# powerblade_3v2.net
KiCad netlist of a schematic drawn in EAGLE
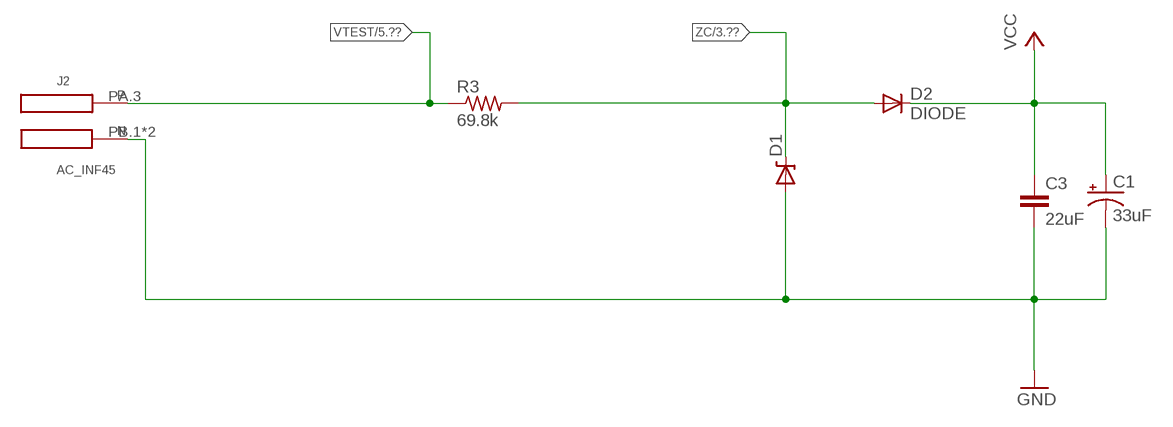
[diagram p0: schematic, sheet 1]
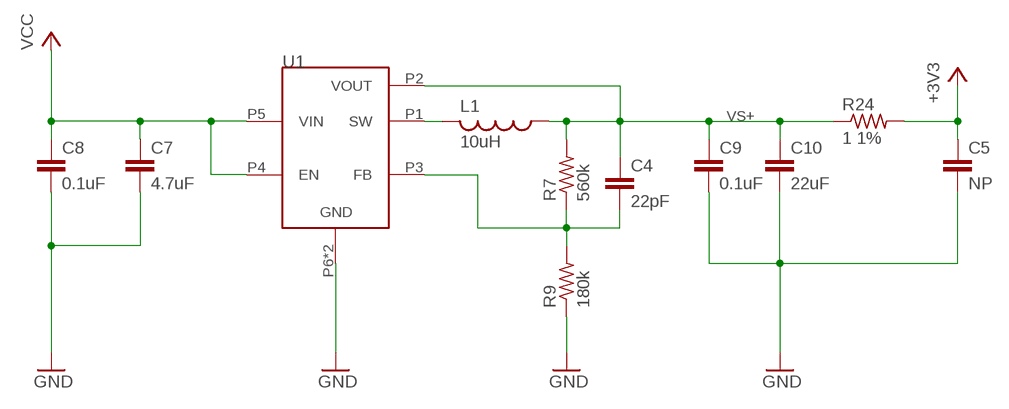
[diagram p1: schematic, sheet 2]
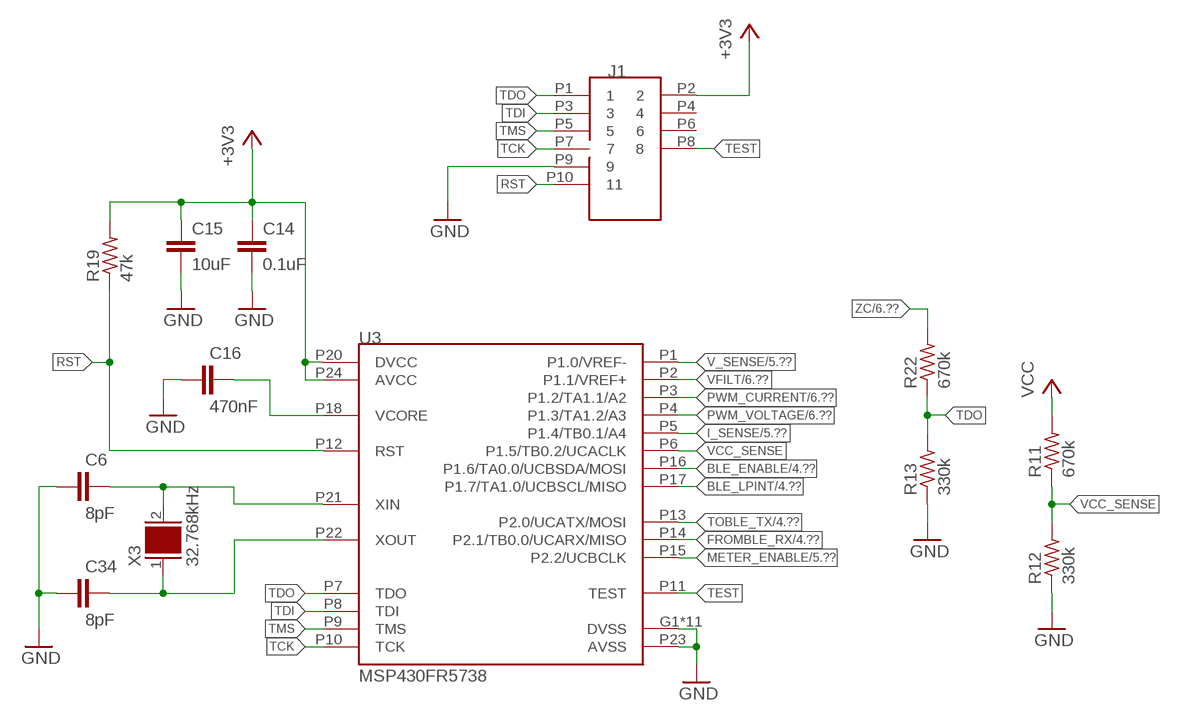
[diagram p2: schematic, sheet 3]
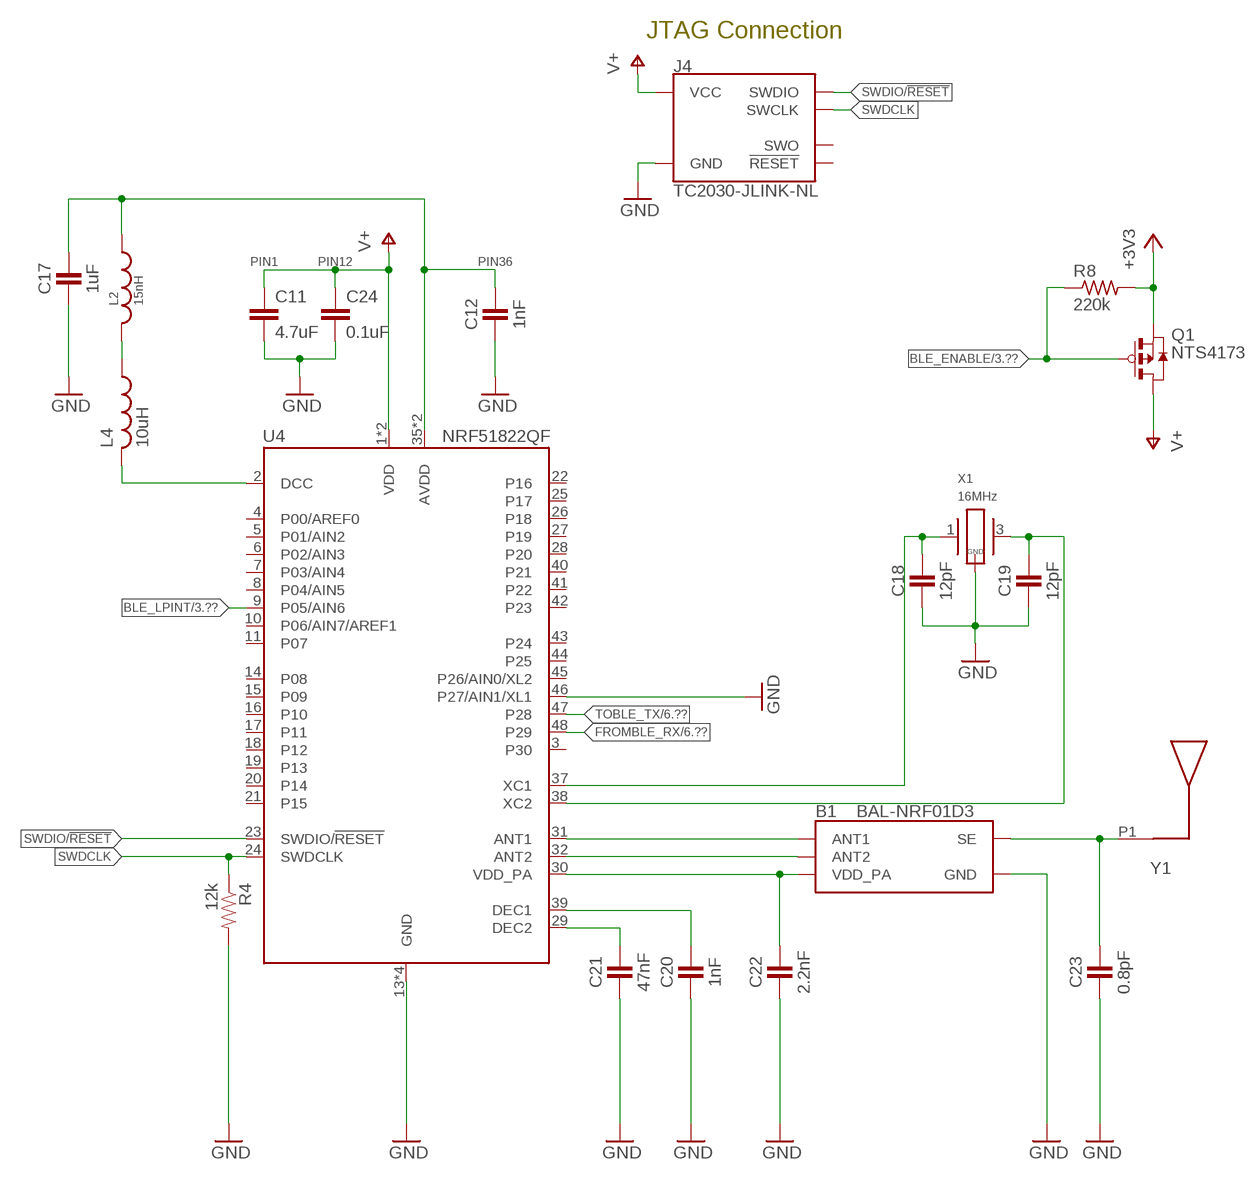
[diagram p3: schematic, sheet 4]
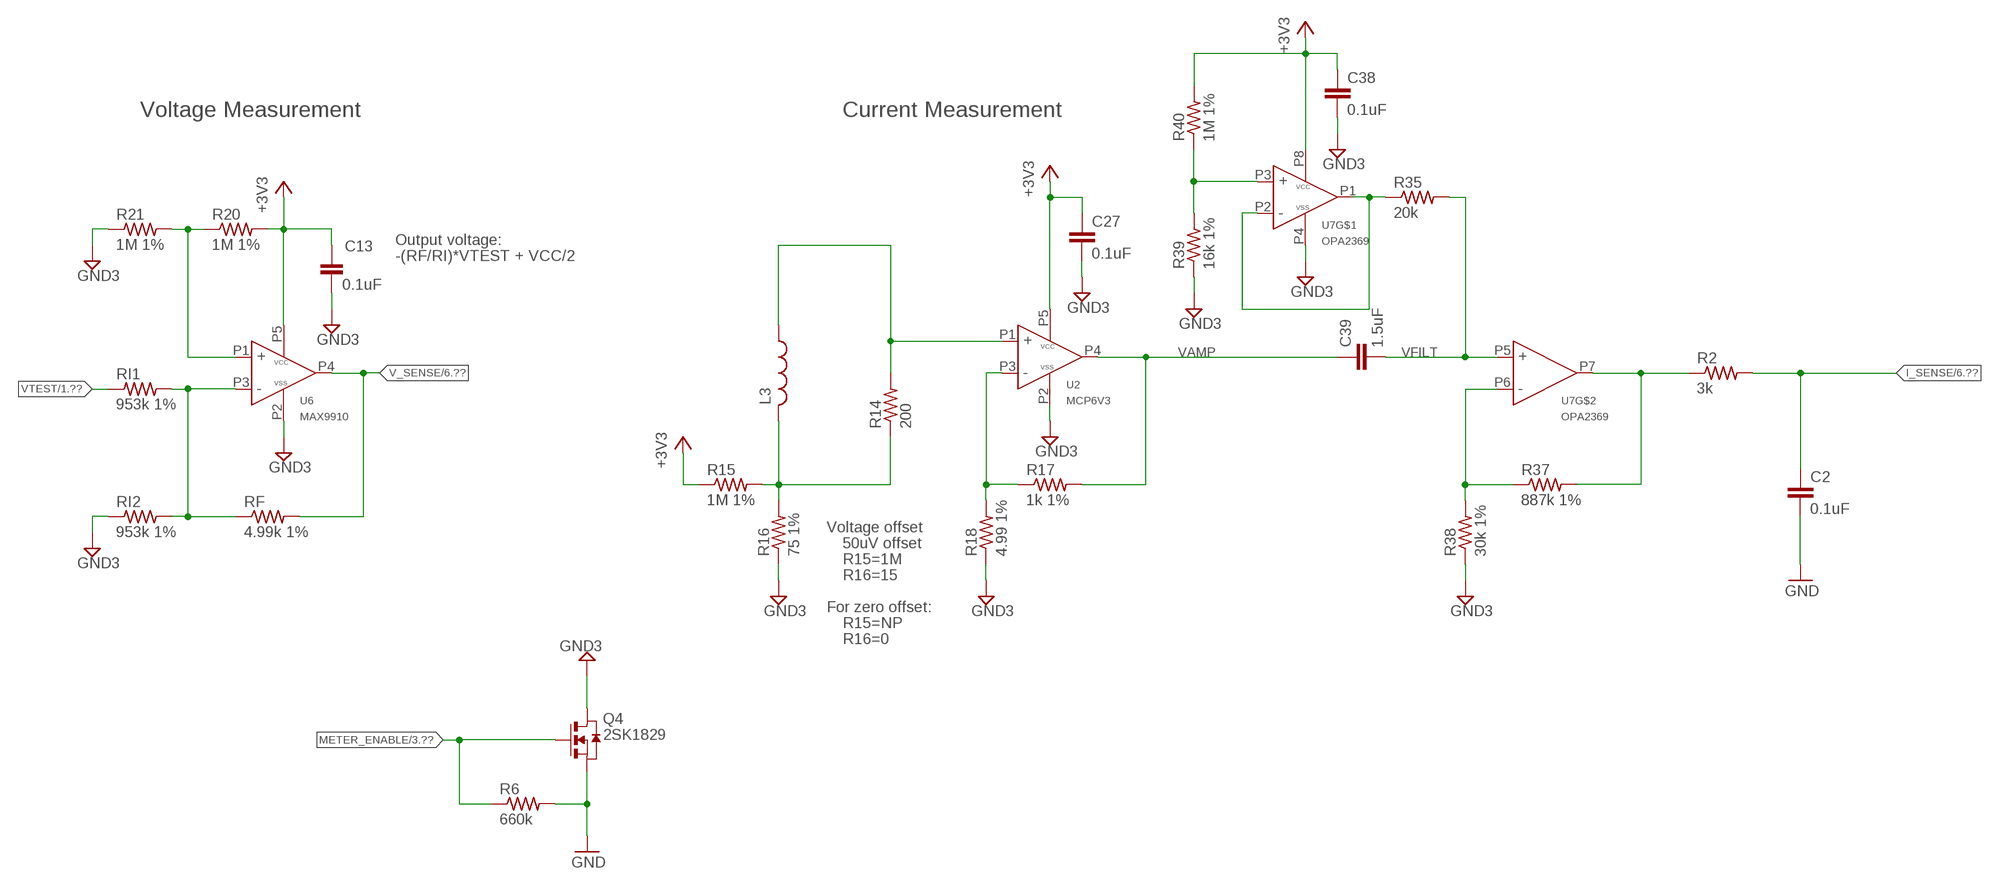
[diagram p4: schematic, sheet 5]
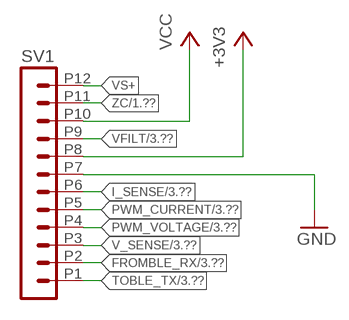
[diagram p5: schematic, sheet 6]

(export (version "E")
  (design (tool "Eeschema 10.0.6"))
  (components
    (comp (ref "C6")
      (value "8pF")
      (footprint "eagle-import:C0402")
      (libsource (lib "eagle-import") (part "C-EUC0402"))
    )
    (comp (ref "C14")
      (value "0.1uF")
      (footprint "eagle-import:C0402")
      (libsource (lib "eagle-import") (part "C-EUC0402"))
    )
    (comp (ref "C15")
      (value "10uF")
      (footprint "eagle-import:C0603_SM")
      (libsource (lib "eagle-import") (part "C-EUC0603_SM"))
    )
    (comp (ref "C16")
      (value "470nF")
      (footprint "eagle-import:C0402")
      (libsource (lib "eagle-import") (part "C-EUC0402"))
    )
    (comp (ref "C34")
      (value "8pF")
      (footprint "eagle-import:C0402")
      (libsource (lib "eagle-import") (part "C-EUC0402"))
    )
    (comp (ref "J1")
      (value "JTAG_14PIN_IDC-ND")
      (footprint "eagle-import:TC2050-IDC-NL-430-ND")
      (libsource (lib "eagle-import") (part "JTAG_14PIN_IDC-ND"))
    )
    (comp (ref "R11")
      (value "670k")
      (footprint "eagle-import:R0402")
      (libsource (lib "eagle-import") (part "R-US_R0402"))
    )
    (comp (ref "R12")
      (value "330k")
      (footprint "eagle-import:R0402")
      (libsource (lib "eagle-import") (part "R-US_R0402"))
    )
    (comp (ref "R13")
      (value "330k")
      (footprint "eagle-import:R0402")
      (libsource (lib "eagle-import") (part "R-US_R0402"))
    )
    (comp (ref "R19")
      (value "47k")
      (footprint "eagle-import:R0402")
      (libsource (lib "eagle-import") (part "R-US_R0402"))
    )
    (comp (ref "R22")
      (value "670k")
      (footprint "eagle-import:R0402")
      (libsource (lib "eagle-import") (part "R-US_R0402"))
    )
    (comp (ref "U3")
      (value "MSP430FR5738")
      (footprint "eagle-import:VQFN-24")
      (libsource (lib "eagle-import") (part "MSP430FR5738"))
    )
    (comp (ref "X3")
      (value "32.768kHz")
      (footprint "eagle-import:0805")
      (libsource (lib "eagle-import") (part "CRYSTAL_0805"))
    )
    (comp (ref "C1")
      (value "33uF")
      (footprint "eagle-import:CPOL0805_SM")
      (libsource (lib "eagle-import") (part "CPOL-US0805_SM"))
    )
    (comp (ref "C3")
      (value "22uF")
      (footprint "eagle-import:C0603_SM")
      (libsource (lib "eagle-import") (part "C-EUC0603_SM"))
    )
    (comp (ref "D1")
      (value "ZENERBZT52")
      (footprint "eagle-import:BZT52")
      (fields (field (name "DIGIKEY") "BZT52C10T-7DICT-ND "))
      (libsource (lib "eagle-import") (part "ZENERBZT52"))
    )
    (comp (ref "D2")
      (value "DIODE")
      (footprint "eagle-import:BAS521")
      (libsource (lib "eagle-import") (part "DIODE"))
    )
    (comp (ref "J2")
      (value "AC_INF45")
      (footprint "eagle-import:AC3_F45")
      (libsource (lib "eagle-import") (part "AC_INF45"))
    )
    (comp (ref "R3")
      (value "69.8k")
      (footprint "eagle-import:R1210")
      (libsource (lib "eagle-import") (part "R-US_R1210"))
    )
    (comp (ref "C4")
      (value "22pF")
      (footprint "eagle-import:C0402")
      (libsource (lib "eagle-import") (part "C-EUC0402"))
    )
    (comp (ref "C5")
      (value "NP")
      (footprint "eagle-import:C0603_TN")
      (libsource (lib "eagle-import") (part "C-EUC0603_TN"))
    )
    (comp (ref "C7")
      (value "4.7uF")
      (footprint "eagle-import:C0402")
      (libsource (lib "eagle-import") (part "C-EUC0402"))
    )
    (comp (ref "C8")
      (value "0.1uF")
      (footprint "eagle-import:C0402")
      (libsource (lib "eagle-import") (part "C-EUC0402"))
    )
    (comp (ref "C9")
      (value "0.1uF")
      (footprint "eagle-import:C0402_SM")
      (libsource (lib "eagle-import") (part "C-EUC0402_SM"))
    )
    (comp (ref "C10")
      (value "22uF")
      (footprint "eagle-import:C0603_SM")
      (libsource (lib "eagle-import") (part "C-EUC0603_SM"))
    )
    (comp (ref "L1")
      (value "10uH")
      (footprint "eagle-import:L0805")
      (libsource (lib "eagle-import") (part "L-USL0805"))
    )
    (comp (ref "R7")
      (value "560k")
      (footprint "eagle-import:R0402")
      (libsource (lib "eagle-import") (part "R-US_R0402"))
    )
    (comp (ref "R9")
      (value "180k")
      (footprint "eagle-import:R0402")
      (libsource (lib "eagle-import") (part "R-US_R0402"))
    )
    (comp (ref "R24")
      (value "1 1%")
      (footprint "eagle-import:R0603_SM")
      (libsource (lib "eagle-import") (part "R-US_R0603_SM"))
    )
    (comp (ref "U1")
      (value "TPS62122")
      (footprint "eagle-import:WDFN-6")
      (libsource (lib "eagle-import") (part "TPS62122"))
    )
    (comp (ref "SV1")
      (value "MA12-11M27")
      (footprint "eagle-import:MA12-1_1MM27")
      (libsource (lib "eagle-import") (part "MA12-11M27"))
    )
    (comp (ref "B1")
      (value "BAL-NRF01D3")
      (footprint "eagle-import:BAL-NRF01D3")
      (libsource (lib "eagle-import") (part "BAL-NRF01D3"))
    )
    (comp (ref "C11")
      (value "4.7uF")
      (footprint "eagle-import:C0402")
      (libsource (lib "eagle-import") (part "C-EUC0402"))
    )
    (comp (ref "C12")
      (value "1nF")
      (footprint "eagle-import:0402_CAP")
      (libsource (lib "eagle-import") (part "CAPACITOR"))
    )
    (comp (ref "C17")
      (value "1uF")
      (footprint "eagle-import:0402_CAP")
      (libsource (lib "eagle-import") (part "CAPACITOR"))
    )
    (comp (ref "C18")
      (value "12pF")
      (footprint "eagle-import:0402_CAP")
      (libsource (lib "eagle-import") (part "CAPACITOR"))
    )
    (comp (ref "C19")
      (value "12pF")
      (footprint "eagle-import:0402_CAP")
      (libsource (lib "eagle-import") (part "CAPACITOR"))
    )
    (comp (ref "C20")
      (value "1nF")
      (footprint "eagle-import:0402_CAP")
      (libsource (lib "eagle-import") (part "CAPACITOR"))
    )
    (comp (ref "C21")
      (value "47nF")
      (footprint "eagle-import:0402_CAP")
      (libsource (lib "eagle-import") (part "CAPACITOR"))
    )
    (comp (ref "C22")
      (value "2.2nF")
      (footprint "eagle-import:0402_CAP")
      (libsource (lib "eagle-import") (part "CAPACITOR"))
    )
    (comp (ref "C23")
      (value "0.8pF")
      (footprint "eagle-import:0402_CAP")
      (libsource (lib "eagle-import") (part "CAPACITOR"))
    )
    (comp (ref "C24")
      (value "0.1uF")
      (footprint "eagle-import:C0402")
      (libsource (lib "eagle-import") (part "C-EUC0402"))
    )
    (comp (ref "J4")
      (value "TC2030-JLINK-NL")
      (footprint "eagle-import:TC2030-IDC-NL")
      (libsource (lib "eagle-import") (part "TC2030-JLINK-NL"))
    )
    (comp (ref "L2")
      (value "15nH")
      (footprint "eagle-import:0402_CAP")
      (libsource (lib "eagle-import") (part "INDUCTOR0402"))
    )
    (comp (ref "L4")
      (value "10uH")
      (footprint "eagle-import:C0603_TN")
      (libsource (lib "eagle-import") (part "L-USL0603_TN"))
    )
    (comp (ref "Q1")
      (value "NTS4173")
      (footprint "eagle-import:SC-70-3")
      (libsource (lib "eagle-import") (part "NTS4173"))
    )
    (comp (ref "R4")
      (value "12k")
      (footprint "eagle-import:0402_RES")
      (libsource (lib "eagle-import") (part "RESISTOR"))
    )
    (comp (ref "R8")
      (value "220k")
      (footprint "eagle-import:R0402_SM")
      (libsource (lib "eagle-import") (part "R-US_R0402_SM"))
    )
    (comp (ref "U4")
      (value "NRF51822QF")
      (footprint "eagle-import:QFN-48-6MM")
      (libsource (lib "eagle-import") (part "NRF51822QF"))
    )
    (comp (ref "X1")
      (value "16MHz")
      (footprint "eagle-import:TXC-8Y")
      (libsource (lib "eagle-import") (part "TXC-8Y"))
    )
    (comp (ref "Y1")
      (value "UREACH_XTEND")
      (footprint "eagle-import:UREACH_XTEND")
      (libsource (lib "eagle-import") (part "UREACH_XTEND"))
    )
    (comp (ref "C2")
      (value "0.1uF")
      (footprint "eagle-import:C0402")
      (libsource (lib "eagle-import") (part "C-EUC0402"))
    )
    (comp (ref "C13")
      (value "0.1uF")
      (footprint "eagle-import:0402_CAP")
      (libsource (lib "eagle-import") (part "CAPACITOR"))
    )
    (comp (ref "C27")
      (value "0.1uF")
      (footprint "eagle-import:C0402")
      (libsource (lib "eagle-import") (part "C-EUC0402"))
    )
    (comp (ref "C38")
      (value "0.1uF")
      (footprint "eagle-import:C0402")
      (libsource (lib "eagle-import") (part "C-EUC0402"))
    )
    (comp (ref "C39")
      (value "1.5uF")
      (footprint "eagle-import:C0402")
      (libsource (lib "eagle-import") (part "C-EUC0402"))
    )
    (comp (ref "L3")
      (value "L-USL0805")
      (footprint "eagle-import:L0805")
      (libsource (lib "eagle-import") (part "L-USL0805"))
    )
    (comp (ref "Q4")
      (value "2SK1829")
      (footprint "eagle-import:SC-70-3")
      (libsource (lib "eagle-import") (part "2SK1829"))
    )
    (comp (ref "R2")
      (value "3k")
      (footprint "eagle-import:R0402_SM")
      (libsource (lib "eagle-import") (part "R-US_R0402_SM"))
    )
    (comp (ref "R6")
      (value "660k")
      (footprint "eagle-import:R0402")
      (libsource (lib "eagle-import") (part "R-US_R0402"))
    )
    (comp (ref "R14")
      (value "200")
      (footprint "eagle-import:R0402")
      (libsource (lib "eagle-import") (part "R-US_R0402"))
    )
    (comp (ref "R15")
      (value "1M 1%")
      (footprint "eagle-import:R0402")
      (libsource (lib "eagle-import") (part "R-US_R0402"))
    )
    (comp (ref "R16")
      (value "75 1%")
      (footprint "eagle-import:R0402")
      (libsource (lib "eagle-import") (part "R-US_R0402"))
    )
    (comp (ref "R17")
      (value "1k 1%")
      (footprint "eagle-import:R0402")
      (libsource (lib "eagle-import") (part "R-US_R0402"))
    )
    (comp (ref "R18")
      (value "4.99 1%")
      (footprint "eagle-import:R0402")
      (libsource (lib "eagle-import") (part "R-US_R0402"))
    )
    (comp (ref "R20")
      (value "1M 1%")
      (footprint "eagle-import:R0402")
      (libsource (lib "eagle-import") (part "R-US_R0402"))
    )
    (comp (ref "R21")
      (value "1M 1%")
      (footprint "eagle-import:R0402_SM")
      (libsource (lib "eagle-import") (part "R-US_R0402_SM"))
    )
    (comp (ref "R35")
      (value "20k")
      (footprint "eagle-import:R0402")
      (libsource (lib "eagle-import") (part "R-US_R0402"))
    )
    (comp (ref "R37")
      (value "887k 1%")
      (footprint "eagle-import:R0402")
      (libsource (lib "eagle-import") (part "R-US_R0402"))
    )
    (comp (ref "R38")
      (value "30k 1%")
      (footprint "eagle-import:R0402")
      (libsource (lib "eagle-import") (part "R-US_R0402"))
    )
    (comp (ref "R39")
      (value "16k 1%")
      (footprint "eagle-import:R0402")
      (libsource (lib "eagle-import") (part "R-US_R0402"))
    )
    (comp (ref "R40")
      (value "1M 1%")
      (footprint "eagle-import:R0402")
      (libsource (lib "eagle-import") (part "R-US_R0402"))
    )
    (comp (ref "RF")
      (value "4.99k 1%")
      (footprint "eagle-import:R0402")
      (libsource (lib "eagle-import") (part "R-US_R0402"))
    )
    (comp (ref "RI1")
      (value "953k 1%")
      (footprint "eagle-import:R0402")
      (libsource (lib "eagle-import") (part "R-US_R0402"))
    )
    (comp (ref "RI2")
      (value "953k 1%")
      (footprint "eagle-import:R0402")
      (libsource (lib "eagle-import") (part "R-US_R0402"))
    )
    (comp (ref "U2")
      (value "MCP6V3")
      (footprint "eagle-import:SC70-5")
      (fields (field (name "DIGIKEY") "296-19547-1-ND"))
      (libsource (lib "eagle-import") (part "MCP6V3"))
    )
    (comp (ref "U6")
      (value "MAX9910")
      (footprint "eagle-import:SC70-5")
      (fields (field (name "DIGIKEY") "296-25252-1-ND"))
      (libsource (lib "eagle-import") (part "MAX9910"))
    )
    (comp (ref "U7")
      (value "OPA2369")
      (footprint "eagle-import:SOT-23-8")
      (libsource (lib "eagle-import") (part "OPA2369"))
    )
  )
  (nets
    (net (code "1") (name "+3V3") (class "Default")
      (node (ref "C13") (pin "1") (pinfunction "1_1") (pintype "bidirectional"))
      (node (ref "C14") (pin "1") (pinfunction "1_1") (pintype "passive"))
      (node (ref "C15") (pin "1") (pinfunction "1_1") (pintype "passive"))
      (node (ref "C27") (pin "1") (pinfunction "1_1") (pintype "passive"))
      (node (ref "C38") (pin "1") (pinfunction "1_1") (pintype "passive"))
      (node (ref "C5") (pin "1") (pinfunction "1_1") (pintype "passive"))
      (node (ref "J1") (pin "P2") (pinfunction "2_P2") (pintype "bidirectional"))
      (node (ref "Q1") (pin "P2") (pinfunction "S_P2") (pintype "passive"))
      (node (ref "R15") (pin "1") (pinfunction "1_1") (pintype "passive"))
      (node (ref "R19") (pin "2") (pinfunction "2_2") (pintype "passive"))
      (node (ref "R20") (pin "2") (pinfunction "2_2") (pintype "passive"))
      (node (ref "R24") (pin "2") (pinfunction "2_2") (pintype "passive"))
      (node (ref "R40") (pin "2") (pinfunction "2_2") (pintype "passive"))
      (node (ref "R8") (pin "2") (pinfunction "2_2") (pintype "passive"))
      (node (ref "SV1") (pin "P8") (pinfunction "8_P8") (pintype "passive"))
      (node (ref "U2") (pin "P5") (pinfunction "VCC_P5") (pintype "bidirectional"))
      (node (ref "U3") (pin "P20") (pinfunction "DVCC_P20") (pintype "bidirectional"))
      (node (ref "U3") (pin "P24") (pinfunction "AVCC_P24") (pintype "bidirectional"))
      (node (ref "U6") (pin "P5") (pinfunction "VCC_P5") (pintype "bidirectional"))
      (node (ref "U7") (pin "P8") (pinfunction "VCC_P8") (pintype "bidirectional"))
    )
    (net (code "2") (name "BLE_ENABLE") (class "Default")
      (node (ref "Q1") (pin "P1") (pinfunction "G_P1") (pintype "passive"))
      (node (ref "R8") (pin "1") (pinfunction "1_1") (pintype "passive"))
      (node (ref "U3") (pin "P16") (pinfunction "P1.6/TA0.0/UCBSDA/MOSI_P16") (pintype "bidirectional"))
    )
    (net (code "3") (name "BLE_LPINT") (class "Default")
      (node (ref "U3") (pin "P17") (pinfunction "P1.7/TA1.0/UCBSCL/MISO_P17") (pintype "bidirectional"))
      (node (ref "U4") (pin "9") (pinfunction "P05/AIN6_9") (pintype "bidirectional"))
    )
    (net (code "4") (name "FROMBLE_RX") (class "Default")
      (node (ref "SV1") (pin "P2") (pinfunction "2_P2") (pintype "passive"))
      (node (ref "U3") (pin "P14") (pinfunction "P2.1/TB0.0/UCARX/MISO_P14") (pintype "bidirectional"))
      (node (ref "U4") (pin "48") (pinfunction "P29_48") (pintype "bidirectional"))
    )
    (net (code "5") (name "GND") (class "Default")
      (node (ref "B1") (pin "GND") (pinfunction "GND_GND") (pintype "bidirectional"))
      (node (ref "C1") (pin "-") (pinfunction "-_-") (pintype "passive"))
      (node (ref "C10") (pin "2") (pinfunction "2_2") (pintype "passive"))
      (node (ref "C11") (pin "2") (pinfunction "2_2") (pintype "passive"))
      (node (ref "C12") (pin "2") (pinfunction "2_2") (pintype "bidirectional"))
      (node (ref "C14") (pin "2") (pinfunction "2_2") (pintype "passive"))
      (node (ref "C15") (pin "2") (pinfunction "2_2") (pintype "passive"))
      (node (ref "C16") (pin "1") (pinfunction "1_1") (pintype "passive"))
      (node (ref "C17") (pin "2") (pinfunction "2_2") (pintype "bidirectional"))
      (node (ref "C18") (pin "2") (pinfunction "2_2") (pintype "bidirectional"))
      (node (ref "C19") (pin "2") (pinfunction "2_2") (pintype "bidirectional"))
      (node (ref "C2") (pin "2") (pinfunction "2_2") (pintype "passive"))
      (node (ref "C20") (pin "2") (pinfunction "2_2") (pintype "bidirectional"))
      (node (ref "C21") (pin "2") (pinfunction "2_2") (pintype "bidirectional"))
      (node (ref "C22") (pin "2") (pinfunction "2_2") (pintype "bidirectional"))
      (node (ref "C23") (pin "2") (pinfunction "2_2") (pintype "bidirectional"))
      (node (ref "C24") (pin "2") (pinfunction "2_2") (pintype "passive"))
      (node (ref "C3") (pin "2") (pinfunction "2_2") (pintype "passive"))
      (node (ref "C34") (pin "1") (pinfunction "1_1") (pintype "passive"))
      (node (ref "C5") (pin "2") (pinfunction "2_2") (pintype "passive"))
      (node (ref "C6") (pin "1") (pinfunction "1_1") (pintype "passive"))
      (node (ref "C7") (pin "2") (pinfunction "2_2") (pintype "passive"))
      (node (ref "C8") (pin "2") (pinfunction "2_2") (pintype "passive"))
      (node (ref "C9") (pin "2") (pinfunction "2_2") (pintype "passive"))
      (node (ref "D1") (pin "A") (pinfunction "A_A") (pintype "passive"))
      (node (ref "J1") (pin "P9") (pinfunction "9_P9") (pintype "bidirectional"))
      (node (ref "J2") (pin "PB.1") (pinfunction "N_PB.1") (pintype "bidirectional"))
      (node (ref "J2") (pin "PB.3") (pinfunction "N_PB.3") (pintype "bidirectional"))
      (node (ref "J4") (pin "5") (pinfunction "GND_5") (pintype "bidirectional"))
      (node (ref "Q4") (pin "P2") (pinfunction "S_P2") (pintype "passive"))
      (node (ref "R12") (pin "1") (pinfunction "1_1") (pintype "passive"))
      (node (ref "R13") (pin "1") (pinfunction "1_1") (pintype "passive"))
      (node (ref "R4") (pin "2") (pinfunction "2_2") (pintype "passive"))
      (node (ref "R6") (pin "2") (pinfunction "2_2") (pintype "passive"))
      (node (ref "R9") (pin "1") (pinfunction "1_1") (pintype "passive"))
      (node (ref "SV1") (pin "P7") (pinfunction "7_P7") (pintype "passive"))
      (node (ref "U1") (pin "P6") (pinfunction "GND_P6") (pintype "bidirectional"))
      (node (ref "U1") (pin "PAD") (pinfunction "GND_PAD") (pintype "bidirectional"))
      (node (ref "U3") (pin "G1") (pinfunction "DVSS_G1") (pintype "bidirectional"))
      (node (ref "U3") (pin "G2") (pinfunction "DVSS_G2") (pintype "bidirectional"))
      (node (ref "U3") (pin "G3") (pinfunction "DVSS_G3") (pintype "bidirectional"))
      (node (ref "U3") (pin "G4") (pinfunction "DVSS_G4") (pintype "bidirectional"))
      (node (ref "U3") (pin "G5") (pinfunction "DVSS_G5") (pintype "bidirectional"))
      (node (ref "U3") (pin "G6") (pinfunction "DVSS_G6") (pintype "bidirectional"))
      (node (ref "U3") (pin "G7") (pinfunction "DVSS_G7") (pintype "bidirectional"))
      (node (ref "U3") (pin "G8") (pinfunction "DVSS_G8") (pintype "bidirectional"))
      (node (ref "U3") (pin "G9") (pinfunction "DVSS_G9") (pintype "bidirectional"))
      (node (ref "U3") (pin "P19") (pinfunction "DVSS_P19") (pintype "bidirectional"))
      (node (ref "U3") (pin "P23") (pinfunction "AVSS_P23") (pintype "bidirectional"))
      (node (ref "U3") (pin "PAD") (pinfunction "DVSS_PAD") (pintype "bidirectional"))
      (node (ref "U4") (pin "13") (pinfunction "GND_13") (pintype "bidirectional"))
      (node (ref "U4") (pin "33") (pinfunction "GND_33") (pintype "bidirectional"))
      (node (ref "U4") (pin "34") (pinfunction "GND_34") (pintype "bidirectional"))
      (node (ref "U4") (pin "46") (pinfunction "P27/AIN1/XL1_46") (pintype "bidirectional"))
      (node (ref "U4") (pin "GND") (pinfunction "GND_GND") (pintype "bidirectional"))
      (node (ref "X1") (pin "2") (pinfunction "GND_2") (pintype "bidirectional"))
      (node (ref "X1") (pin "4") (pinfunction "GND_4") (pintype "bidirectional"))
    )
    (net (code "6") (name "GND3") (class "Default")
      (node (ref "C13") (pin "2") (pinfunction "2_2") (pintype "bidirectional"))
      (node (ref "C27") (pin "2") (pinfunction "2_2") (pintype "passive"))
      (node (ref "C38") (pin "2") (pinfunction "2_2") (pintype "passive"))
      (node (ref "Q4") (pin "P3") (pinfunction "D_P3") (pintype "passive"))
      (node (ref "R16") (pin "1") (pinfunction "1_1") (pintype "passive"))
      (node (ref "R18") (pin "1") (pinfunction "1_1") (pintype "passive"))
      (node (ref "R21") (pin "1") (pinfunction "1_1") (pintype "passive"))
      (node (ref "R38") (pin "1") (pinfunction "1_1") (pintype "passive"))
      (node (ref "R39") (pin "1") (pinfunction "1_1") (pintype "passive"))
      (node (ref "RI2") (pin "1") (pinfunction "1_1") (pintype "passive"))
      (node (ref "U2") (pin "P2") (pinfunction "VSS_P2") (pintype "bidirectional"))
      (node (ref "U6") (pin "P2") (pinfunction "VSS_P2") (pintype "bidirectional"))
      (node (ref "U7") (pin "P4") (pinfunction "VSS_P4") (pintype "bidirectional"))
    )
    (net (code "7") (name "I_SENSE") (class "Default")
      (node (ref "C2") (pin "1") (pinfunction "1_1") (pintype "passive"))
      (node (ref "R2") (pin "2") (pinfunction "2_2") (pintype "passive"))
      (node (ref "SV1") (pin "P6") (pinfunction "6_P6") (pintype "passive"))
      (node (ref "U3") (pin "P5") (pinfunction "P1.4/TB0.1/A4_P5") (pintype "bidirectional"))
    )
    (net (code "8") (name "METER_ENABLE") (class "Default")
      (node (ref "Q4") (pin "P1") (pinfunction "G_P1") (pintype "passive"))
      (node (ref "R6") (pin "1") (pinfunction "1_1") (pintype "passive"))
      (node (ref "U3") (pin "P15") (pinfunction "P2.2/UCBCLK_P15") (pintype "bidirectional"))
    )
    (net (code "9") (name "Net-(B1-PadSE)") (class "Default")
      (node (ref "B1") (pin "SE") (pinfunction "SE_SE") (pintype "bidirectional"))
      (node (ref "C23") (pin "1") (pinfunction "1_1") (pintype "bidirectional"))
      (node (ref "Y1") (pin "P1") (pinfunction "P1_P1") (pintype "bidirectional"))
    )
    (net (code "10") (name "Net-(B1-VDD_PA)") (class "Default")
      (node (ref "B1") (pin "VCC") (pinfunction "VDD_PA_VCC") (pintype "bidirectional"))
      (node (ref "C22") (pin "1") (pinfunction "1_1") (pintype "bidirectional"))
      (node (ref "U4") (pin "30") (pinfunction "VDD_PA_30") (pintype "bidirectional"))
    )
    (net (code "11") (name "Net-(C12-Pad1)") (class "Default")
      (node (ref "C12") (pin "1") (pinfunction "1_1") (pintype "bidirectional"))
      (node (ref "C17") (pin "1") (pinfunction "1_1") (pintype "bidirectional"))
      (node (ref "L2") (pin "1") (pinfunction "1_1") (pintype "bidirectional"))
      (node (ref "U4") (pin "35") (pinfunction "AVDD_35") (pintype "bidirectional"))
      (node (ref "U4") (pin "36") (pinfunction "AVDD_36") (pintype "bidirectional"))
    )
    (net (code "12") (name "Net-(L2-Pad2)") (class "Default")
      (node (ref "L2") (pin "2") (pinfunction "2_2") (pintype "bidirectional"))
      (node (ref "L4") (pin "1") (pinfunction "1_1") (pintype "passive"))
    )
    (net (code "13") (name "Net-(L3-Pad2)") (class "Default")
      (node (ref "L3") (pin "2") (pinfunction "2_2") (pintype "passive"))
      (node (ref "R14") (pin "1") (pinfunction "1_1") (pintype "passive"))
      (node (ref "R15") (pin "2") (pinfunction "2_2") (pintype "passive"))
      (node (ref "R16") (pin "2") (pinfunction "2_2") (pintype "passive"))
    )
    (net (code "14") (name "Net-(U1-FB)") (class "Default")
      (node (ref "C4") (pin "2") (pinfunction "2_2") (pintype "passive"))
      (node (ref "R7") (pin "1") (pinfunction "1_1") (pintype "passive"))
      (node (ref "R9") (pin "2") (pinfunction "2_2") (pintype "passive"))
      (node (ref "U1") (pin "P3") (pinfunction "FB_P3") (pintype "bidirectional"))
    )
    (net (code "15") (name "Net-(U1-SW)") (class "Default")
      (node (ref "L1") (pin "2") (pinfunction "2_2") (pintype "passive"))
      (node (ref "U1") (pin "P1") (pinfunction "SW_P1") (pintype "bidirectional"))
    )
    (net (code "16") (name "Net-(U2-IN+)") (class "Default")
      (node (ref "L3") (pin "1") (pinfunction "1_1") (pintype "passive"))
      (node (ref "R14") (pin "2") (pinfunction "2_2") (pintype "passive"))
      (node (ref "U2") (pin "P1") (pinfunction "IN+_P1") (pintype "bidirectional"))
    )
    (net (code "17") (name "Net-(U2-IN-)") (class "Default")
      (node (ref "R17") (pin "1") (pinfunction "1_1") (pintype "passive"))
      (node (ref "R18") (pin "2") (pinfunction "2_2") (pintype "passive"))
      (node (ref "U2") (pin "P3") (pinfunction "IN-_P3") (pintype "bidirectional"))
    )
    (net (code "18") (name "Net-(U3-VCORE)") (class "Default")
      (node (ref "C16") (pin "2") (pinfunction "2_2") (pintype "passive"))
      (node (ref "U3") (pin "P18") (pinfunction "VCORE_P18") (pintype "bidirectional"))
    )
    (net (code "19") (name "Net-(U3-XIN)") (class "Default")
      (node (ref "C6") (pin "2") (pinfunction "2_2") (pintype "passive"))
      (node (ref "U3") (pin "P21") (pinfunction "XIN_P21") (pintype "bidirectional"))
      (node (ref "X3") (pin "2") (pinfunction "P2_2") (pintype "bidirectional"))
    )
    (net (code "20") (name "Net-(U3-XOUT)") (class "Default")
      (node (ref "C34") (pin "2") (pinfunction "2_2") (pintype "passive"))
      (node (ref "U3") (pin "P22") (pinfunction "XOUT_P22") (pintype "bidirectional"))
      (node (ref "X3") (pin "1") (pinfunction "P1_1") (pintype "bidirectional"))
    )
    (net (code "21") (name "Net-(U4-ANT1)") (class "Default")
      (node (ref "B1") (pin "ANT1") (pinfunction "ANT1_ANT1") (pintype "bidirectional"))
      (node (ref "U4") (pin "31") (pinfunction "ANT1_31") (pintype "bidirectional"))
    )
    (net (code "22") (name "Net-(U4-ANT2)") (class "Default")
      (node (ref "B1") (pin "ANT2") (pinfunction "ANT2_ANT2") (pintype "bidirectional"))
      (node (ref "U4") (pin "32") (pinfunction "ANT2_32") (pintype "bidirectional"))
    )
    (net (code "23") (name "Net-(U4-DCC)") (class "Default")
      (node (ref "L4") (pin "2") (pinfunction "2_2") (pintype "passive"))
      (node (ref "U4") (pin "2") (pinfunction "DCC_2") (pintype "bidirectional"))
    )
    (net (code "24") (name "Net-(U4-DEC1)") (class "Default")
      (node (ref "C20") (pin "1") (pinfunction "1_1") (pintype "bidirectional"))
      (node (ref "U4") (pin "39") (pinfunction "DEC1_39") (pintype "bidirectional"))
    )
    (net (code "25") (name "Net-(U4-DEC2)") (class "Default")
      (node (ref "C21") (pin "1") (pinfunction "1_1") (pintype "bidirectional"))
      (node (ref "U4") (pin "29") (pinfunction "DEC2_29") (pintype "bidirectional"))
    )
    (net (code "26") (name "Net-(U4-XC1)") (class "Default")
      (node (ref "C18") (pin "1") (pinfunction "1_1") (pintype "bidirectional"))
      (node (ref "U4") (pin "37") (pinfunction "XC1_37") (pintype "bidirectional"))
      (node (ref "X1") (pin "1") (pinfunction "1_1") (pintype "bidirectional"))
    )
    (net (code "27") (name "Net-(U4-XC2)") (class "Default")
      (node (ref "C19") (pin "1") (pinfunction "1_1") (pintype "bidirectional"))
      (node (ref "U4") (pin "38") (pinfunction "XC2_38") (pintype "bidirectional"))
      (node (ref "X1") (pin "3") (pinfunction "2_3") (pintype "bidirectional"))
    )
    (net (code "28") (name "Net-(U6-IN+)") (class "Default")
      (node (ref "R20") (pin "1") (pinfunction "1_1") (pintype "passive"))
      (node (ref "R21") (pin "2") (pinfunction "2_2") (pintype "passive"))
      (node (ref "U6") (pin "P1") (pinfunction "IN+_P1") (pintype "bidirectional"))
    )
    (net (code "29") (name "Net-(U6-IN-)") (class "Default")
      (node (ref "RF") (pin "1") (pinfunction "1_1") (pintype "passive"))
      (node (ref "RI1") (pin "2") (pinfunction "2_2") (pintype "passive"))
      (node (ref "RI2") (pin "2") (pinfunction "2_2") (pintype "passive"))
      (node (ref "U6") (pin "P3") (pinfunction "IN-_P3") (pintype "bidirectional"))
    )
    (net (code "30") (name "Net-(U7A-IN+)") (class "Default")
      (node (ref "R39") (pin "2") (pinfunction "2_2") (pintype "passive"))
      (node (ref "R40") (pin "1") (pinfunction "1_1") (pintype "passive"))
      (node (ref "U7") (pin "P3") (pinfunction "IN+_P3") (pintype "bidirectional"))
    )
    (net (code "31") (name "Net-(U7A-IN-)") (class "Default")
      (node (ref "R35") (pin "1") (pinfunction "1_1") (pintype "passive"))
      (node (ref "U7") (pin "P1") (pinfunction "OUT_P1") (pintype "bidirectional"))
      (node (ref "U7") (pin "P2") (pinfunction "IN-_P2") (pintype "bidirectional"))
    )
    (net (code "32") (name "Net-(U7B-IN-)") (class "Default")
      (node (ref "R37") (pin "1") (pinfunction "1_1") (pintype "passive"))
      (node (ref "R38") (pin "2") (pinfunction "2_2") (pintype "passive"))
      (node (ref "U7") (pin "P6") (pinfunction "IN-_P6") (pintype "bidirectional"))
    )
    (net (code "33") (name "Net-(U7B-OUT)") (class "Default")
      (node (ref "R2") (pin "1") (pinfunction "1_1") (pintype "passive"))
      (node (ref "R37") (pin "2") (pinfunction "2_2") (pintype "passive"))
      (node (ref "U7") (pin "P7") (pinfunction "OUT_P7") (pintype "bidirectional"))
    )
    (net (code "34") (name "PWM_CURRENT") (class "Default")
      (node (ref "SV1") (pin "P5") (pinfunction "5_P5") (pintype "passive"))
      (node (ref "U3") (pin "P3") (pinfunction "P1.2/TA1.1/A2_P3") (pintype "bidirectional"))
    )
    (net (code "35") (name "PWM_VOLTAGE") (class "Default")
      (node (ref "SV1") (pin "P4") (pinfunction "4_P4") (pintype "passive"))
      (node (ref "U3") (pin "P4") (pinfunction "P1.3/TA1.2/A3_P4") (pintype "bidirectional"))
    )
    (net (code "36") (name "RST") (class "Default")
      (node (ref "J1") (pin "P10") (pinfunction "11_P10") (pintype "bidirectional"))
      (node (ref "R19") (pin "1") (pinfunction "1_1") (pintype "passive"))
      (node (ref "U3") (pin "P12") (pinfunction "RST_P12") (pintype "bidirectional"))
    )
    (net (code "37") (name "SWDCLK") (class "Default")
      (node (ref "J4") (pin "4") (pinfunction "SWCLK_4") (pintype "bidirectional"))
      (node (ref "R4") (pin "1") (pinfunction "1_1") (pintype "passive"))
      (node (ref "U4") (pin "24") (pinfunction "SWDCLK_24") (pintype "bidirectional"))
    )
    (net (code "38") (name "SWDIO{slash}~{RESET}") (class "Default")
      (node (ref "J4") (pin "2") (pinfunction "SWDIO_2") (pintype "bidirectional"))
      (node (ref "U4") (pin "23") (pinfunction "SWDIO/~{RESET}_23") (pintype "bidirectional"))
    )
    (net (code "39") (name "TCK") (class "Default")
      (node (ref "J1") (pin "P7") (pinfunction "7_P7") (pintype "bidirectional"))
      (node (ref "U3") (pin "P10") (pinfunction "TCK_P10") (pintype "bidirectional"))
    )
    (net (code "40") (name "TDI") (class "Default")
      (node (ref "J1") (pin "P3") (pinfunction "3_P3") (pintype "bidirectional"))
      (node (ref "U3") (pin "P8") (pinfunction "TDI_P8") (pintype "bidirectional"))
    )
    (net (code "41") (name "TDO") (class "Default")
      (node (ref "J1") (pin "P1") (pinfunction "1_P1") (pintype "bidirectional"))
      (node (ref "R13") (pin "2") (pinfunction "2_2") (pintype "passive"))
      (node (ref "R22") (pin "1") (pinfunction "1_1") (pintype "passive"))
      (node (ref "U3") (pin "P7") (pinfunction "TDO_P7") (pintype "bidirectional"))
    )
    (net (code "42") (name "TEST") (class "Default")
      (node (ref "J1") (pin "P8") (pinfunction "8_P8") (pintype "bidirectional"))
      (node (ref "U3") (pin "P11") (pinfunction "TEST_P11") (pintype "bidirectional"))
    )
    (net (code "43") (name "TMS") (class "Default")
      (node (ref "J1") (pin "P5") (pinfunction "5_P5") (pintype "bidirectional"))
      (node (ref "U3") (pin "P9") (pinfunction "TMS_P9") (pintype "bidirectional"))
    )
    (net (code "44") (name "TOBLE_TX") (class "Default")
      (node (ref "SV1") (pin "P1") (pinfunction "1_P1") (pintype "passive"))
      (node (ref "U3") (pin "P13") (pinfunction "P2.0/UCATX/MOSI_P13") (pintype "bidirectional"))
      (node (ref "U4") (pin "47") (pinfunction "P28_47") (pintype "bidirectional"))
    )
    (net (code "45") (name "V+") (class "Default")
      (node (ref "C11") (pin "1") (pinfunction "1_1") (pintype "passive"))
      (node (ref "C24") (pin "1") (pinfunction "1_1") (pintype "passive"))
      (node (ref "J4") (pin "1") (pinfunction "VCC_1") (pintype "bidirectional"))
      (node (ref "Q1") (pin "P3") (pinfunction "D_P3") (pintype "passive"))
      (node (ref "U4") (pin "1") (pinfunction "VDD_1") (pintype "bidirectional"))
      (node (ref "U4") (pin "12") (pinfunction "VDD_12") (pintype "bidirectional"))
    )
    (net (code "46") (name "VAMP") (class "Default")
      (node (ref "C39") (pin "1") (pinfunction "1_1") (pintype "passive"))
      (node (ref "R17") (pin "2") (pinfunction "2_2") (pintype "passive"))
      (node (ref "U2") (pin "P4") (pinfunction "OUT_P4") (pintype "bidirectional"))
    )
    (net (code "47") (name "VCC") (class "Default")
      (node (ref "C1") (pin "+") (pinfunction "+_+") (pintype "passive"))
      (node (ref "C3") (pin "1") (pinfunction "1_1") (pintype "passive"))
      (node (ref "C7") (pin "1") (pinfunction "1_1") (pintype "passive"))
      (node (ref "C8") (pin "1") (pinfunction "1_1") (pintype "passive"))
      (node (ref "D2") (pin "C") (pinfunction "C_C") (pintype "passive"))
      (node (ref "R11") (pin "2") (pinfunction "2_2") (pintype "passive"))
      (node (ref "SV1") (pin "P10") (pinfunction "10_P10") (pintype "passive"))
      (node (ref "U1") (pin "P4") (pinfunction "EN_P4") (pintype "bidirectional"))
      (node (ref "U1") (pin "P5") (pinfunction "VIN_P5") (pintype "bidirectional"))
    )
    (net (code "48") (name "VCC_SENSE") (class "Default")
      (node (ref "R11") (pin "1") (pinfunction "1_1") (pintype "passive"))
      (node (ref "R12") (pin "2") (pinfunction "2_2") (pintype "passive"))
      (node (ref "U3") (pin "P6") (pinfunction "P1.5/TB0.2/UCACLK_P6") (pintype "bidirectional"))
    )
    (net (code "49") (name "VFILT") (class "Default")
      (node (ref "C39") (pin "2") (pinfunction "2_2") (pintype "passive"))
      (node (ref "R35") (pin "2") (pinfunction "2_2") (pintype "passive"))
      (node (ref "SV1") (pin "P9") (pinfunction "9_P9") (pintype "passive"))
      (node (ref "U3") (pin "P2") (pinfunction "P1.1/VREF+_P2") (pintype "bidirectional"))
      (node (ref "U7") (pin "P5") (pinfunction "IN+_P5") (pintype "bidirectional"))
    )
    (net (code "50") (name "VS+") (class "Default")
      (node (ref "C10") (pin "1") (pinfunction "1_1") (pintype "passive"))
      (node (ref "C4") (pin "1") (pinfunction "1_1") (pintype "passive"))
      (node (ref "C9") (pin "1") (pinfunction "1_1") (pintype "passive"))
      (node (ref "L1") (pin "1") (pinfunction "1_1") (pintype "passive"))
      (node (ref "R24") (pin "1") (pinfunction "1_1") (pintype "passive"))
      (node (ref "R7") (pin "2") (pinfunction "2_2") (pintype "passive"))
      (node (ref "SV1") (pin "P12") (pinfunction "12_P12") (pintype "passive"))
      (node (ref "U1") (pin "P2") (pinfunction "VOUT_P2") (pintype "bidirectional"))
    )
    (net (code "51") (name "VTEST") (class "Default")
      (node (ref "J2") (pin "PA.3") (pinfunction "P_PA.3") (pintype "bidirectional"))
      (node (ref "R3") (pin "1") (pinfunction "1_1") (pintype "passive"))
      (node (ref "RI1") (pin "1") (pinfunction "1_1") (pintype "passive"))
    )
    (net (code "52") (name "V_SENSE") (class "Default")
      (node (ref "RF") (pin "2") (pinfunction "2_2") (pintype "passive"))
      (node (ref "SV1") (pin "P3") (pinfunction "3_P3") (pintype "passive"))
      (node (ref "U3") (pin "P1") (pinfunction "P1.0/VREF-_P1") (pintype "bidirectional"))
      (node (ref "U6") (pin "P4") (pinfunction "OUT_P4") (pintype "bidirectional"))
    )
    (net (code "53") (name "ZC") (class "Default")
      (node (ref "D1") (pin "C") (pinfunction "C_C") (pintype "passive"))
      (node (ref "D2") (pin "A") (pinfunction "A_A") (pintype "passive"))
      (node (ref "R22") (pin "2") (pinfunction "2_2") (pintype "passive"))
      (node (ref "R3") (pin "2") (pinfunction "2_2") (pintype "passive"))
      (node (ref "SV1") (pin "P11") (pinfunction "11_P11") (pintype "passive"))
    )
    (net (code "54") (name "unconnected-(J1-4-PadP4)") (class "Default")
      (node (ref "J1") (pin "P4") (pinfunction "4_P4") (pintype "bidirectional"))
    )
    (net (code "55") (name "unconnected-(J1-6-PadP6)") (class "Default")
      (node (ref "J1") (pin "P6") (pinfunction "6_P6") (pintype "bidirectional"))
    )
    (net (code "56") (name "unconnected-(J4-SWO-Pad6)") (class "Default")
      (node (ref "J4") (pin "6") (pinfunction "SWO_6") (pintype "bidirectional"))
    )
    (net (code "57") (name "unconnected-(J4-~{RESET}-Pad3)") (class "Default")
      (node (ref "J4") (pin "3") (pinfunction "~{RESET}_3") (pintype "bidirectional"))
    )
    (net (code "58") (name "unconnected-(U4-P00{slash}AREF0-Pad4)") (class "Default")
      (node (ref "U4") (pin "4") (pinfunction "P00/AREF0_4") (pintype "bidirectional"))
    )
    (net (code "59") (name "unconnected-(U4-P01{slash}AIN2-Pad5)") (class "Default")
      (node (ref "U4") (pin "5") (pinfunction "P01/AIN2_5") (pintype "bidirectional"))
    )
    (net (code "60") (name "unconnected-(U4-P02{slash}AIN3-Pad6)") (class "Default")
      (node (ref "U4") (pin "6") (pinfunction "P02/AIN3_6") (pintype "bidirectional"))
    )
    (net (code "61") (name "unconnected-(U4-P03{slash}AIN4-Pad7)") (class "Default")
      (node (ref "U4") (pin "7") (pinfunction "P03/AIN4_7") (pintype "bidirectional"))
    )
    (net (code "62") (name "unconnected-(U4-P04{slash}AIN5-Pad8)") (class "Default")
      (node (ref "U4") (pin "8") (pinfunction "P04/AIN5_8") (pintype "bidirectional"))
    )
    (net (code "63") (name "unconnected-(U4-P06{slash}AIN7{slash}AREF1-Pad10)") (class "Default")
      (node (ref "U4") (pin "10") (pinfunction "P06/AIN7/AREF1_10") (pintype "bidirectional"))
    )
    (net (code "64") (name "unconnected-(U4-P07-Pad11)") (class "Default")
      (node (ref "U4") (pin "11") (pinfunction "P07_11") (pintype "bidirectional"))
    )
    (net (code "65") (name "unconnected-(U4-P08-Pad14)") (class "Default")
      (node (ref "U4") (pin "14") (pinfunction "P08_14") (pintype "bidirectional"))
    )
    (net (code "66") (name "unconnected-(U4-P09-Pad15)") (class "Default")
      (node (ref "U4") (pin "15") (pinfunction "P09_15") (pintype "bidirectional"))
    )
    (net (code "67") (name "unconnected-(U4-P10-Pad16)") (class "Default")
      (node (ref "U4") (pin "16") (pinfunction "P10_16") (pintype "bidirectional"))
    )
    (net (code "68") (name "unconnected-(U4-P11-Pad17)") (class "Default")
      (node (ref "U4") (pin "17") (pinfunction "P11_17") (pintype "bidirectional"))
    )
    (net (code "69") (name "unconnected-(U4-P12-Pad18)") (class "Default")
      (node (ref "U4") (pin "18") (pinfunction "P12_18") (pintype "bidirectional"))
    )
    (net (code "70") (name "unconnected-(U4-P13-Pad19)") (class "Default")
      (node (ref "U4") (pin "19") (pinfunction "P13_19") (pintype "bidirectional"))
    )
    (net (code "71") (name "unconnected-(U4-P14-Pad20)") (class "Default")
      (node (ref "U4") (pin "20") (pinfunction "P14_20") (pintype "bidirectional"))
    )
    (net (code "72") (name "unconnected-(U4-P15-Pad21)") (class "Default")
      (node (ref "U4") (pin "21") (pinfunction "P15_21") (pintype "bidirectional"))
    )
    (net (code "73") (name "unconnected-(U4-P16-Pad22)") (class "Default")
      (node (ref "U4") (pin "22") (pinfunction "P16_22") (pintype "bidirectional"))
    )
    (net (code "74") (name "unconnected-(U4-P17-Pad25)") (class "Default")
      (node (ref "U4") (pin "25") (pinfunction "P17_25") (pintype "bidirectional"))
    )
    (net (code "75") (name "unconnected-(U4-P18-Pad26)") (class "Default")
      (node (ref "U4") (pin "26") (pinfunction "P18_26") (pintype "bidirectional"))
    )
    (net (code "76") (name "unconnected-(U4-P19-Pad27)") (class "Default")
      (node (ref "U4") (pin "27") (pinfunction "P19_27") (pintype "bidirectional"))
    )
    (net (code "77") (name "unconnected-(U4-P20-Pad28)") (class "Default")
      (node (ref "U4") (pin "28") (pinfunction "P20_28") (pintype "bidirectional"))
    )
    (net (code "78") (name "unconnected-(U4-P21-Pad40)") (class "Default")
      (node (ref "U4") (pin "40") (pinfunction "P21_40") (pintype "bidirectional"))
    )
    (net (code "79") (name "unconnected-(U4-P22-Pad41)") (class "Default")
      (node (ref "U4") (pin "41") (pinfunction "P22_41") (pintype "bidirectional"))
    )
    (net (code "80") (name "unconnected-(U4-P23-Pad42)") (class "Default")
      (node (ref "U4") (pin "42") (pinfunction "P23_42") (pintype "bidirectional"))
    )
    (net (code "81") (name "unconnected-(U4-P24-Pad43)") (class "Default")
      (node (ref "U4") (pin "43") (pinfunction "P24_43") (pintype "bidirectional"))
    )
    (net (code "82") (name "unconnected-(U4-P25-Pad44)") (class "Default")
      (node (ref "U4") (pin "44") (pinfunction "P25_44") (pintype "bidirectional"))
    )
    (net (code "83") (name "unconnected-(U4-P26{slash}AIN0{slash}XL2-Pad45)") (class "Default")
      (node (ref "U4") (pin "45") (pinfunction "P26/AIN0/XL2_45") (pintype "bidirectional"))
    )
    (net (code "84") (name "unconnected-(U4-P30-Pad3)") (class "Default")
      (node (ref "U4") (pin "3") (pinfunction "P30_3") (pintype "bidirectional"))
    )
  )
)
